# MCU.net
KiCad netlist of a schematic drawn in Altium Designer
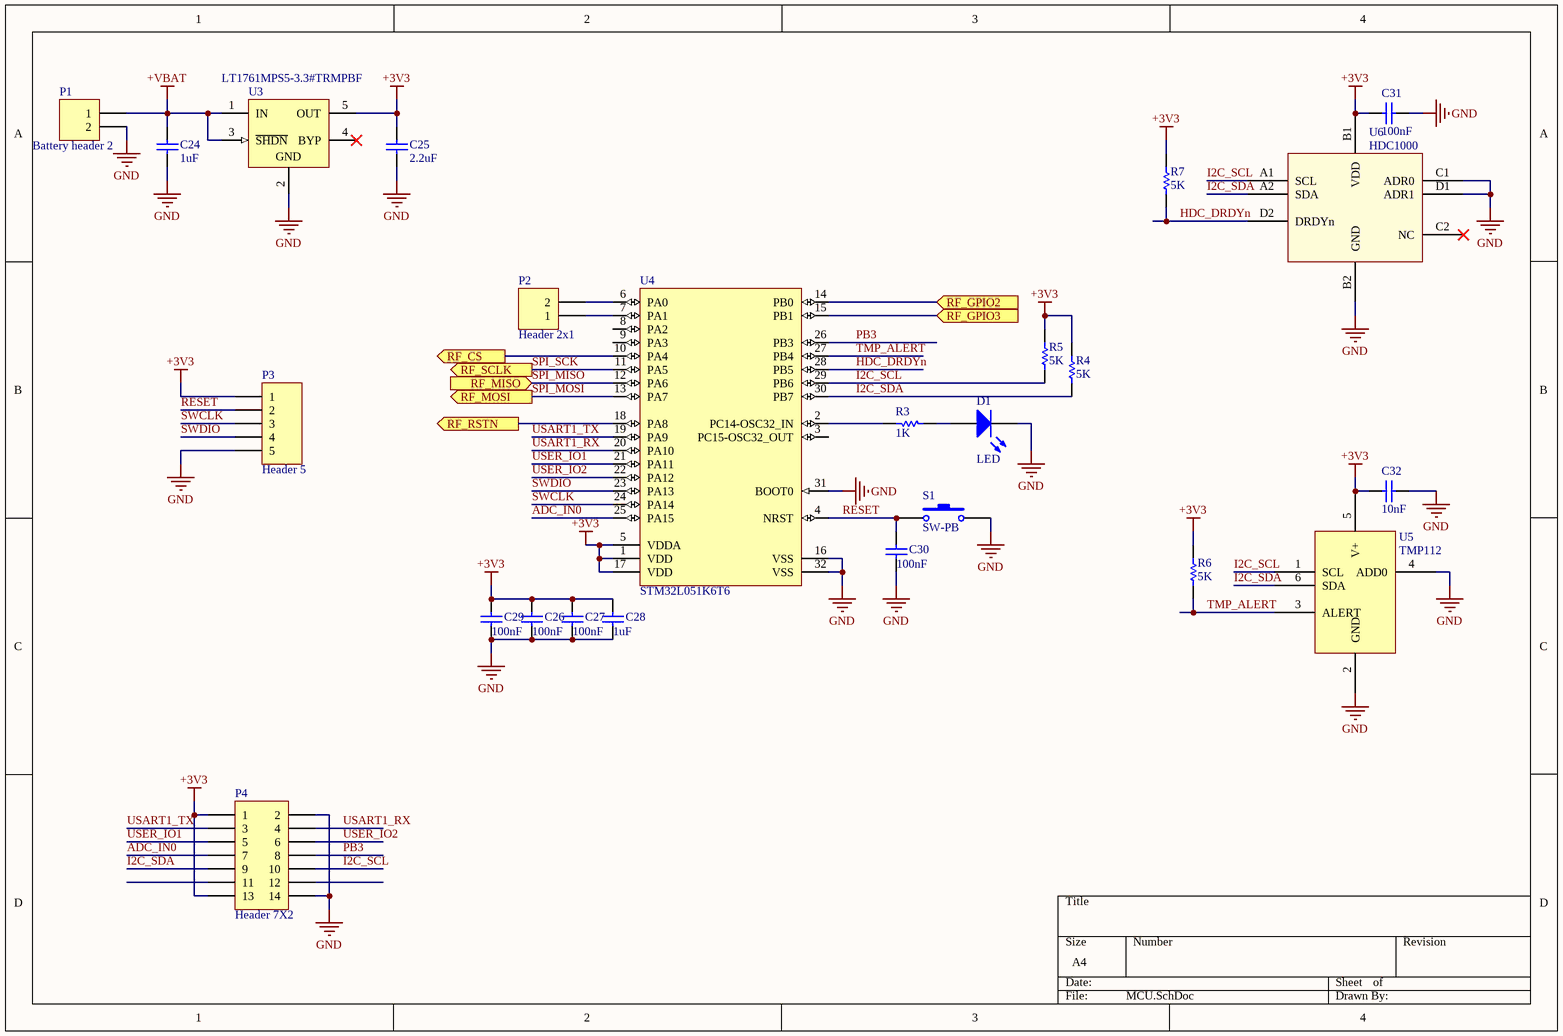
[diagram p0: MCU.SchDoc]

(export (version "E")
  (design (tool "Eeschema 10.0.6"))
  (components
    (comp (ref "C24")
      (value "1uF")
      (footprint "0402_ipc")
      (description "Capacitor")
      (fields (field (name "Comment") "Cap") (field (name "PUBLISHER") "Altium Limited"))
      (libsource (lib "LucasLib") (part "Cap"))
    )
    (comp (ref "C25")
      (value "2.2uF")
      (footprint "0402_ipc")
      (description "Capacitor")
      (fields (field (name "Comment") "Cap") (field (name "PUBLISHER") "Altium Limited"))
      (libsource (lib "LucasLib") (part "Cap"))
    )
    (comp (ref "C26")
      (value "100nF")
      (footprint "0402_ipc")
      (description "Capacitor")
      (fields (field (name "Comment") "Cap") (field (name "PUBLISHER") "Altium Limited"))
      (libsource (lib "LucasLib") (part "Cap"))
    )
    (comp (ref "C27")
      (value "100nF")
      (footprint "0402_ipc")
      (description "Capacitor")
      (fields (field (name "Comment") "Cap") (field (name "PUBLISHER") "Altium Limited"))
      (libsource (lib "LucasLib") (part "Cap"))
    )
    (comp (ref "C28")
      (value "1uF")
      (footprint "0402_ipc")
      (description "Capacitor")
      (fields (field (name "Comment") "Cap") (field (name "PUBLISHER") "Altium Limited"))
      (libsource (lib "LucasLib") (part "Cap"))
    )
    (comp (ref "C29")
      (value "100nF")
      (footprint "0402_ipc")
      (description "Capacitor")
      (fields (field (name "Comment") "Cap") (field (name "PUBLISHER") "Altium Limited"))
      (libsource (lib "LucasLib") (part "Cap"))
    )
    (comp (ref "C30")
      (value "100nF")
      (footprint "0402_ipc")
      (description "Capacitor")
      (fields (field (name "Comment") "Cap") (field (name "PUBLISHER") "Altium Limited"))
      (libsource (lib "LucasLib") (part "Cap"))
    )
    (comp (ref "C31")
      (value "100nF")
      (footprint "0402_ipc")
      (description "Capacitor")
      (fields (field (name "Comment") "Cap") (field (name "PUBLISHER") "Altium Limited"))
      (libsource (lib "LucasLib") (part "Cap"))
    )
    (comp (ref "C32")
      (value "10nF")
      (footprint "0402_ipc")
      (description "Capacitor")
      (fields (field (name "Comment") "Cap") (field (name "PUBLISHER") "Altium Limited"))
      (libsource (lib "LucasLib") (part "Cap"))
    )
    (comp (ref "D1")
      (value "LED")
      (footprint "LED_5MM")
      (description "Typical INFRARED GaAs LED")
      (fields (field (name "PUBLISHER") "Altium Limited"))
      (libsource (lib "LucasLib") (part "LED"))
    )
    (comp (ref "P1")
      (value "Battery header 2")
      (footprint "HDR1X2")
      (fields (field (name "PUBLISHER") "Altium Limited"))
      (libsource (lib "LucasLib") (part "Battery header 2"))
    )
    (comp (ref "P2")
      (value "Header 2x1")
      (footprint "HDR1X2_100mil")
      (libsource (lib "LucasLib") (part "Header 2x1"))
    )
    (comp (ref "P3")
      (value "Header 5")
      (footprint "HDR1X5")
      (description "Header, 5-Pin")
      (fields (field (name "PUBLISHER") "Altium Limited"))
      (libsource (lib "Miscellaneous Connectors") (part "Header 5"))
    )
    (comp (ref "P4")
      (value "Header 7X2")
      (footprint "HDR2X7")
      (description "Header, 7-Pin, Dual row")
      (fields (field (name "PUBLISHER") "Altium Limited"))
      (libsource (lib "Miscellaneous Connectors") (part "Header 7X2"))
    )
    (comp (ref "R3")
      (value "1K")
      (footprint "0805_IPC")
      (description "Resistor")
      (fields (field (name "Comment") "Res"))
      (libsource (lib "LucasLib") (part "Res"))
    )
    (comp (ref "R4")
      (value "5K")
      (footprint "0402_ipc")
      (description "Resistor")
      (fields (field (name "Comment") "Res"))
      (libsource (lib "LucasLib") (part "Res"))
    )
    (comp (ref "R5")
      (value "5K")
      (footprint "0402_ipc")
      (description "Resistor")
      (fields (field (name "Comment") "Res"))
      (libsource (lib "LucasLib") (part "Res"))
    )
    (comp (ref "R6")
      (value "5K")
      (footprint "0402_ipc")
      (description "Resistor")
      (fields (field (name "Comment") "Res"))
      (libsource (lib "LucasLib") (part "Res"))
    )
    (comp (ref "R7")
      (value "5K")
      (footprint "0402_ipc")
      (description "Resistor")
      (fields (field (name "Comment") "Res"))
      (libsource (lib "LucasLib") (part "Res"))
    )
    (comp (ref "S1")
      (value "SW-PB")
      (footprint "SW_PB")
      (description "Switch")
      (fields (field (name "PUBLISHER") "Altium Limited"))
      (libsource (lib "LucasLib") (part "SW-PB"))
    )
    (comp (ref "U3")
      (value "LT1761MPS5-3.3#TRMPBF")
      (footprint "LT-S5-5-TSOT-23_M")
      (fields (field (name "MANUFACTURER") "Linear Technology"))
      (libsource (lib "Altium Content Vault") (part "LT-LTXXXXX-S5-5"))
    )
    (comp (ref "U4")
      (value "STM32L051K6T6")
      (footprint "STM-LQFP32_M")
      (fields (field (name "MANUFACTURER") "STMicroelectronics"))
      (libsource (lib "Altium Content Vault") (part "STM-STM32L051K6-LQFP-32"))
    )
    (comp (ref "U5") (value "TMP112") (footprint "TMP112") (libsource (lib "LucasLib") (part "TMP112")))
    (comp (ref "U6") (value "HDC1000") (footprint "HDC1000") (libsource (lib "LucasLib") (part "HDC1000")))
  )
  (nets
    (net (code "1") (name "+3V3") (class "Default")
      (node (ref "C25") (pin "2") (pinfunction "2_2") (pintype "passive"))
      (node (ref "C26") (pin "2") (pinfunction "2_2") (pintype "passive"))
      (node (ref "C27") (pin "2") (pinfunction "2_2") (pintype "passive"))
      (node (ref "C28") (pin "2") (pinfunction "2_2") (pintype "passive"))
      (node (ref "C29") (pin "2") (pinfunction "2_2") (pintype "passive"))
      (node (ref "C31") (pin "2") (pinfunction "2_2") (pintype "passive"))
      (node (ref "C32") (pin "2") (pinfunction "2_2") (pintype "passive"))
      (node (ref "P3") (pin "1") (pinfunction "1_1") (pintype "passive"))
      (node (ref "P4") (pin "1") (pinfunction "1_1") (pintype "passive"))
      (node (ref "P4") (pin "13") (pinfunction "13_13") (pintype "passive"))
      (node (ref "R4") (pin "2") (pinfunction "2_2") (pintype "passive"))
      (node (ref "R5") (pin "2") (pinfunction "2_2") (pintype "passive"))
      (node (ref "R6") (pin "2") (pinfunction "2_2") (pintype "passive"))
      (node (ref "R7") (pin "2") (pinfunction "2_2") (pintype "passive"))
      (node (ref "U3") (pin "5") (pinfunction "OUT_5") (pintype "power_in"))
      (node (ref "U4") (pin "1") (pinfunction "VDD_1") (pintype "power_in"))
      (node (ref "U4") (pin "17") (pinfunction "VDD_17") (pintype "power_in"))
      (node (ref "U4") (pin "5") (pinfunction "VDDA_5") (pintype "power_in"))
      (node (ref "U5") (pin "5") (pinfunction "V+_5") (pintype "passive"))
      (node (ref "U6") (pin "B1") (pinfunction "VDD_B1") (pintype "passive"))
    )
    (net (code "2") (name "+VBAT") (class "Default")
      (node (ref "C24") (pin "2") (pinfunction "2_2") (pintype "passive"))
      (node (ref "P1") (pin "1") (pinfunction "1_1") (pintype "passive"))
      (node (ref "U3") (pin "1") (pinfunction "IN_1") (pintype "power_in"))
      (node (ref "U3") (pin "3") (pinfunction "~{SHDN}_3") (pintype "input"))
    )
    (net (code "3") (name "/ADC_IN0") (class "Default")
      (node (ref "P4") (pin "7") (pinfunction "7_7") (pintype "passive"))
      (node (ref "U4") (pin "25") (pinfunction "PA15_25") (pintype "bidirectional"))
    )
    (net (code "4") (name "/HDC_DRDYn") (class "Default")
      (node (ref "R7") (pin "1") (pinfunction "1_1") (pintype "passive"))
      (node (ref "U4") (pin "28") (pinfunction "PB5_28") (pintype "bidirectional"))
      (node (ref "U6") (pin "D2") (pinfunction "DRDYn_D2") (pintype "passive"))
    )
    (net (code "5") (name "/I2C_SCL") (class "Default")
      (node (ref "P4") (pin "10") (pinfunction "10_10") (pintype "passive"))
      (node (ref "R5") (pin "1") (pinfunction "1_1") (pintype "passive"))
      (node (ref "U4") (pin "29") (pinfunction "PB6_29") (pintype "bidirectional"))
      (node (ref "U5") (pin "1") (pinfunction "SCL_1") (pintype "passive"))
      (node (ref "U6") (pin "A1") (pinfunction "SCL_A1") (pintype "passive"))
    )
    (net (code "6") (name "/I2C_SDA") (class "Default")
      (node (ref "P4") (pin "9") (pinfunction "9_9") (pintype "passive"))
      (node (ref "R4") (pin "1") (pinfunction "1_1") (pintype "passive"))
      (node (ref "U4") (pin "30") (pinfunction "PB7_30") (pintype "bidirectional"))
      (node (ref "U5") (pin "6") (pinfunction "SDA_6") (pintype "passive"))
      (node (ref "U6") (pin "A2") (pinfunction "SDA_A2") (pintype "passive"))
    )
    (net (code "7") (name "/PB3") (class "Default")
      (node (ref "P4") (pin "8") (pinfunction "8_8") (pintype "passive"))
      (node (ref "U4") (pin "26") (pinfunction "PB3_26") (pintype "bidirectional"))
    )
    (net (code "8") (name "/RESET") (class "Default")
      (node (ref "C30") (pin "2") (pinfunction "2_2") (pintype "passive"))
      (node (ref "P3") (pin "2") (pinfunction "2_2") (pintype "passive"))
      (node (ref "S1") (pin "1") (pinfunction "1_1") (pintype "passive"))
      (node (ref "U4") (pin "4") (pinfunction "NRST_4") (pintype "bidirectional"))
    )
    (net (code "9") (name "/RF_CS") (class "Default")
      (node (ref "U4") (pin "10") (pinfunction "PA4_10") (pintype "bidirectional"))
    )
    (net (code "10") (name "/RF_GPIO2") (class "Default")
      (node (ref "U4") (pin "14") (pinfunction "PB0_14") (pintype "bidirectional"))
    )
    (net (code "11") (name "/RF_GPIO3") (class "Default")
      (node (ref "U4") (pin "15") (pinfunction "PB1_15") (pintype "bidirectional"))
    )
    (net (code "12") (name "/RF_RSTN") (class "Default")
      (node (ref "U4") (pin "18") (pinfunction "PA8_18") (pintype "bidirectional"))
    )
    (net (code "13") (name "/SPI_MISO") (class "Default")
      (node (ref "U4") (pin "12") (pinfunction "PA6_12") (pintype "bidirectional"))
    )
    (net (code "14") (name "/SPI_MOSI") (class "Default")
      (node (ref "U4") (pin "13") (pinfunction "PA7_13") (pintype "bidirectional"))
    )
    (net (code "15") (name "/SPI_SCK") (class "Default")
      (node (ref "U4") (pin "11") (pinfunction "PA5_11") (pintype "bidirectional"))
    )
    (net (code "16") (name "/SWCLK") (class "Default")
      (node (ref "P3") (pin "3") (pinfunction "3_3") (pintype "passive"))
      (node (ref "U4") (pin "24") (pinfunction "PA14_24") (pintype "bidirectional"))
    )
    (net (code "17") (name "/SWDIO") (class "Default")
      (node (ref "P3") (pin "4") (pinfunction "4_4") (pintype "passive"))
      (node (ref "U4") (pin "23") (pinfunction "PA13_23") (pintype "bidirectional"))
    )
    (net (code "18") (name "/TMP_ALERT") (class "Default")
      (node (ref "R6") (pin "1") (pinfunction "1_1") (pintype "passive"))
      (node (ref "U4") (pin "27") (pinfunction "PB4_27") (pintype "bidirectional"))
      (node (ref "U5") (pin "3") (pinfunction "ALERT_3") (pintype "passive"))
    )
    (net (code "19") (name "/USART1_RX") (class "Default")
      (node (ref "P4") (pin "4") (pinfunction "4_4") (pintype "passive"))
      (node (ref "U4") (pin "20") (pinfunction "PA10_20") (pintype "bidirectional"))
    )
    (net (code "20") (name "/USART1_TX") (class "Default")
      (node (ref "P4") (pin "3") (pinfunction "3_3") (pintype "passive"))
      (node (ref "U4") (pin "19") (pinfunction "PA9_19") (pintype "bidirectional"))
    )
    (net (code "21") (name "/USER_IO1") (class "Default")
      (node (ref "P4") (pin "5") (pinfunction "5_5") (pintype "passive"))
      (node (ref "U4") (pin "21") (pinfunction "PA11_21") (pintype "bidirectional"))
    )
    (net (code "22") (name "/USER_IO2") (class "Default")
      (node (ref "P4") (pin "6") (pinfunction "6_6") (pintype "passive"))
      (node (ref "U4") (pin "22") (pinfunction "PA12_22") (pintype "bidirectional"))
    )
    (net (code "23") (name "GND") (class "Default")
      (node (ref "C24") (pin "1") (pinfunction "1_1") (pintype "passive"))
      (node (ref "C25") (pin "1") (pinfunction "1_1") (pintype "passive"))
      (node (ref "C26") (pin "1") (pinfunction "1_1") (pintype "passive"))
      (node (ref "C27") (pin "1") (pinfunction "1_1") (pintype "passive"))
      (node (ref "C28") (pin "1") (pinfunction "1_1") (pintype "passive"))
      (node (ref "C29") (pin "1") (pinfunction "1_1") (pintype "passive"))
      (node (ref "C30") (pin "1") (pinfunction "1_1") (pintype "passive"))
      (node (ref "C31") (pin "1") (pinfunction "1_1") (pintype "passive"))
      (node (ref "C32") (pin "1") (pinfunction "1_1") (pintype "passive"))
      (node (ref "D1") (pin "2") (pinfunction "K_2") (pintype "passive"))
      (node (ref "P1") (pin "2") (pinfunction "2_2") (pintype "passive"))
      (node (ref "P3") (pin "5") (pinfunction "5_5") (pintype "passive"))
      (node (ref "P4") (pin "14") (pinfunction "14_14") (pintype "passive"))
      (node (ref "P4") (pin "2") (pinfunction "2_2") (pintype "passive"))
      (node (ref "S1") (pin "2") (pinfunction "2_2") (pintype "passive"))
      (node (ref "U3") (pin "2") (pinfunction "GND_2") (pintype "power_in"))
      (node (ref "U4") (pin "16") (pinfunction "VSS_16") (pintype "power_in"))
      (node (ref "U4") (pin "31") (pinfunction "BOOT0_31") (pintype "input"))
      (node (ref "U4") (pin "32") (pinfunction "VSS_32") (pintype "power_in"))
      (node (ref "U5") (pin "2") (pinfunction "GND_2") (pintype "passive"))
      (node (ref "U5") (pin "4") (pinfunction "ADD0_4") (pintype "passive"))
      (node (ref "U6") (pin "B2") (pinfunction "GND_B2") (pintype "passive"))
      (node (ref "U6") (pin "C1") (pinfunction "ADR0_C1") (pintype "passive"))
      (node (ref "U6") (pin "D1") (pinfunction "ADR1_D1") (pintype "passive"))
    )
    (net (code "24") (name "Net-(D1-A)") (class "Default")
      (node (ref "D1") (pin "1") (pinfunction "A_1") (pintype "passive"))
      (node (ref "R3") (pin "2") (pinfunction "2_2") (pintype "passive"))
    )
    (net (code "25") (name "Net-(U4-PA0)") (class "Default")
      (node (ref "P2") (pin "2") (pinfunction "2_2") (pintype "passive"))
      (node (ref "U4") (pin "6") (pinfunction "PA0_6") (pintype "bidirectional"))
    )
    (net (code "26") (name "Net-(U4-PA1)") (class "Default")
      (node (ref "P2") (pin "1") (pinfunction "1_1") (pintype "passive"))
      (node (ref "U4") (pin "7") (pinfunction "PA1_7") (pintype "bidirectional"))
    )
    (net (code "27") (name "Net-(U4-PC14-OSC32_IN)") (class "Default")
      (node (ref "R3") (pin "1") (pinfunction "1_1") (pintype "passive"))
      (node (ref "U4") (pin "2") (pinfunction "PC14-OSC32_IN_2") (pintype "bidirectional"))
    )
    (net (code "28") (name "unconnected-(P4-Pad11)") (class "Default")
      (node (ref "P4") (pin "11") (pinfunction "11_11") (pintype "passive"))
    )
    (net (code "29") (name "unconnected-(P4-Pad12)") (class "Default")
      (node (ref "P4") (pin "12") (pinfunction "12_12") (pintype "passive"))
    )
    (net (code "30") (name "unconnected-(U3-BYP-Pad4)") (class "Default")
      (node (ref "U3") (pin "4") (pinfunction "BYP_4") (pintype "passive+no_connect"))
    )
    (net (code "31") (name "unconnected-(U4-PA2-Pad8)") (class "Default")
      (node (ref "U4") (pin "8") (pinfunction "PA2_8") (pintype "bidirectional"))
    )
    (net (code "32") (name "unconnected-(U4-PA3-Pad9)") (class "Default")
      (node (ref "U4") (pin "9") (pinfunction "PA3_9") (pintype "bidirectional"))
    )
    (net (code "33") (name "unconnected-(U4-PC15-OSC32_OUT-Pad3)") (class "Default")
      (node (ref "U4") (pin "3") (pinfunction "PC15-OSC32_OUT_3") (pintype "bidirectional"))
    )
    (net (code "34") (name "unconnected-(U6-NC-PadC2)") (class "Default")
      (node (ref "U6") (pin "C2") (pinfunction "NC_C2") (pintype "passive+no_connect"))
    )
  )
)
